# teste.net
KiCad netlist of a schematic drawn in EAGLE
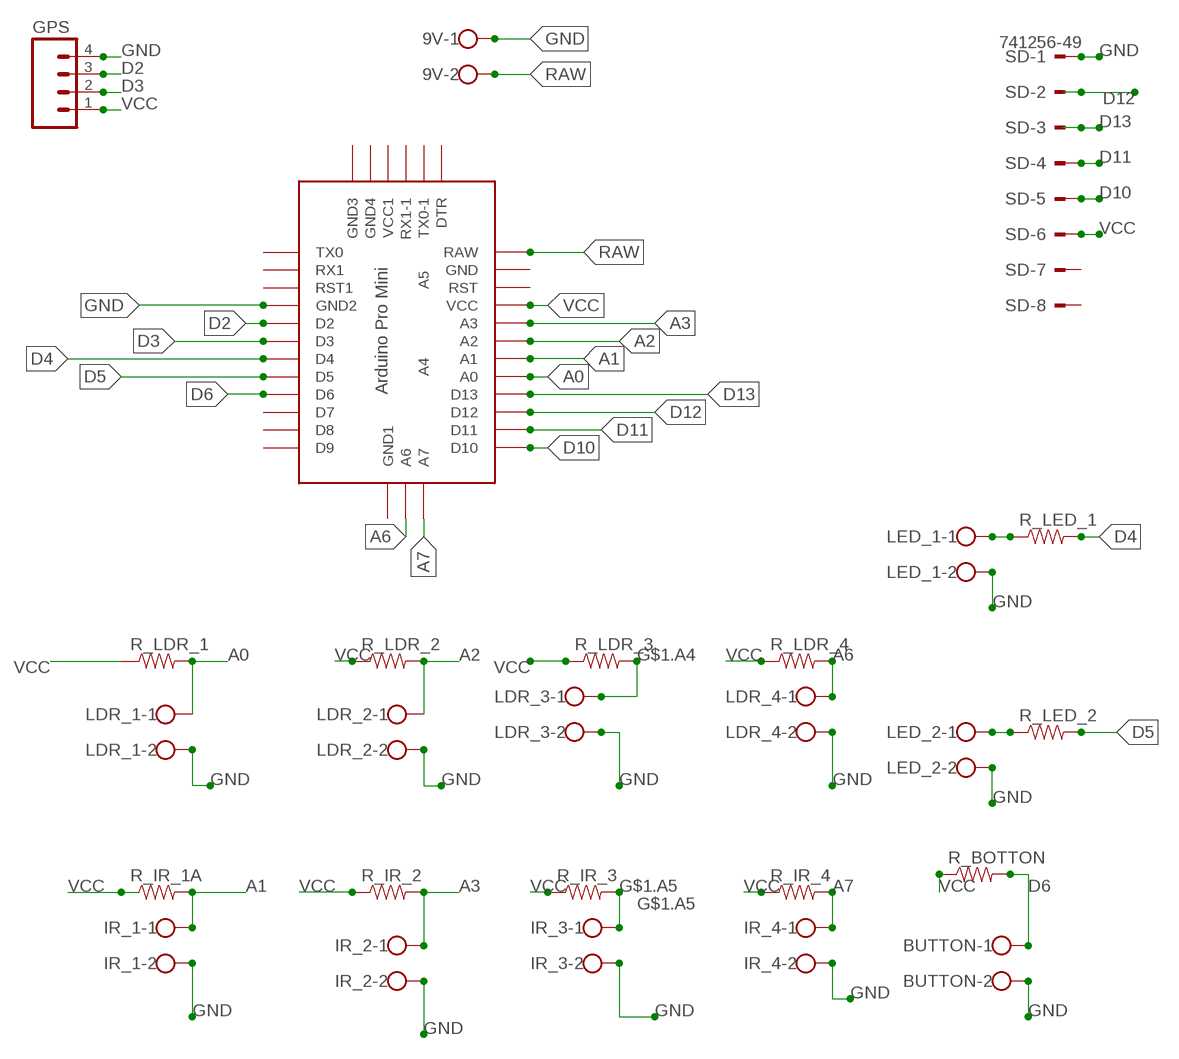
[diagram p0: schematic, sheet 1]

(export (version "E")
  (design (tool "Eeschema 10.0.6"))
  (components
    (comp (ref "9V")
      (value "W237-102")
      (footprint "eagle-import:W237-102")
      (fields (field (name "MPN") "237-102"))
      (libsource (lib "eagle-import") (part "W237-102"))
    )
    (comp (ref "BUTTON")
      (value "W237-102")
      (footprint "eagle-import:W237-102")
      (fields (field (name "MPN") "237-102"))
      (libsource (lib "eagle-import") (part "W237-102"))
    )
    (comp (ref "GPS")
      (value "M04LONGPADS")
      (footprint "eagle-import:1X04_LONGPADS")
      (libsource (lib "eagle-import") (part "M04LONGPADS"))
    )
    (comp (ref "IR_1")
      (value "W237-102")
      (footprint "eagle-import:W237-102")
      (fields (field (name "MPN") "237-102"))
      (libsource (lib "eagle-import") (part "W237-102"))
    )
    (comp (ref "IR_2")
      (value "W237-102")
      (footprint "eagle-import:W237-102")
      (fields (field (name "MPN") "237-102"))
      (libsource (lib "eagle-import") (part "W237-102"))
    )
    (comp (ref "IR_3")
      (value "W237-102")
      (footprint "eagle-import:W237-102")
      (fields (field (name "MPN") "237-102"))
      (libsource (lib "eagle-import") (part "W237-102"))
    )
    (comp (ref "IR_4")
      (value "W237-102")
      (footprint "eagle-import:W237-102")
      (fields (field (name "MPN") "237-102"))
      (libsource (lib "eagle-import") (part "W237-102"))
    )
    (comp (ref "LDR_1")
      (value "W237-102")
      (footprint "eagle-import:W237-102")
      (fields (field (name "MPN") "237-102"))
      (libsource (lib "eagle-import") (part "W237-102"))
    )
    (comp (ref "LDR_2")
      (value "W237-102")
      (footprint "eagle-import:W237-102")
      (fields (field (name "MPN") "237-102"))
      (libsource (lib "eagle-import") (part "W237-102"))
    )
    (comp (ref "LDR_3")
      (value "W237-102")
      (footprint "eagle-import:W237-102")
      (fields (field (name "MPN") "237-102"))
      (libsource (lib "eagle-import") (part "W237-102"))
    )
    (comp (ref "LDR_4")
      (value "W237-102")
      (footprint "eagle-import:W237-102")
      (fields (field (name "MPN") "237-102"))
      (libsource (lib "eagle-import") (part "W237-102"))
    )
    (comp (ref "LED_1")
      (value "W237-102")
      (footprint "eagle-import:W237-102")
      (fields (field (name "MPN") "237-102"))
      (libsource (lib "eagle-import") (part "W237-102"))
    )
    (comp (ref "LED_2")
      (value "W237-102")
      (footprint "eagle-import:W237-102")
      (fields (field (name "MPN") "237-102"))
      (libsource (lib "eagle-import") (part "W237-102"))
    )
    (comp (ref "R_BOTTON")
      (value "RESISTORAXIAL-0.3")
      (footprint "eagle-import:AXIAL-0.3")
      (libsource (lib "eagle-import") (part "RESISTORAXIAL-0.3"))
    )
    (comp (ref "R_IR_1A")
      (value "RESISTORAXIAL-0.3")
      (footprint "eagle-import:AXIAL-0.3")
      (libsource (lib "eagle-import") (part "RESISTORAXIAL-0.3"))
    )
    (comp (ref "R_IR_2")
      (value "RESISTORAXIAL-0.3")
      (footprint "eagle-import:AXIAL-0.3")
      (libsource (lib "eagle-import") (part "RESISTORAXIAL-0.3"))
    )
    (comp (ref "R_IR_3")
      (value "RESISTORAXIAL-0.3")
      (footprint "eagle-import:AXIAL-0.3")
      (libsource (lib "eagle-import") (part "RESISTORAXIAL-0.3"))
    )
    (comp (ref "R_IR_4")
      (value "RESISTORAXIAL-0.3")
      (footprint "eagle-import:AXIAL-0.3")
      (libsource (lib "eagle-import") (part "RESISTORAXIAL-0.3"))
    )
    (comp (ref "R_LDR_1")
      (value "RESISTORAXIAL-0.3")
      (footprint "eagle-import:AXIAL-0.3")
      (libsource (lib "eagle-import") (part "RESISTORAXIAL-0.3"))
    )
    (comp (ref "R_LDR_2")
      (value "RESISTORAXIAL-0.3")
      (footprint "eagle-import:AXIAL-0.3")
      (libsource (lib "eagle-import") (part "RESISTORAXIAL-0.3"))
    )
    (comp (ref "R_LDR_3")
      (value "RESISTORAXIAL-0.3")
      (footprint "eagle-import:AXIAL-0.3")
      (libsource (lib "eagle-import") (part "RESISTORAXIAL-0.3"))
    )
    (comp (ref "R_LDR_4")
      (value "RESISTORAXIAL-0.3")
      (footprint "eagle-import:AXIAL-0.3")
      (libsource (lib "eagle-import") (part "RESISTORAXIAL-0.3"))
    )
    (comp (ref "R_LED_1")
      (value "RESISTORAXIAL-0.3")
      (footprint "eagle-import:AXIAL-0.3")
      (libsource (lib "eagle-import") (part "RESISTORAXIAL-0.3"))
    )
    (comp (ref "R_LED_2")
      (value "RESISTORAXIAL-0.3")
      (footprint "eagle-import:AXIAL-0.3")
      (libsource (lib "eagle-import") (part "RESISTORAXIAL-0.3"))
    )
    (comp (ref "SD")
      (value "741256-49")
      (footprint "eagle-import:741256-49")
      (libsource (lib "eagle-import") (part "741256-49"))
    )
    (comp (ref "U$2")
      (value "ABK-PRO-MINI")
      (footprint "eagle-import:ABK-PRO-MINI")
      (libsource (lib "eagle-import") (part "ABK-PRO-MINI"))
    )
  )
  (nets
    (net (code "1") (name "/G$1.A4") (class "Default")
      (node (ref "LDR_3") (pin "1") (pinfunction "KL_1") (pintype "passive"))
      (node (ref "R_LDR_3") (pin "P$2") (pinfunction "2_P$2") (pintype "passive"))
    )
    (net (code "2") (name "/G$1.A5") (class "Default")
      (node (ref "IR_3") (pin "1") (pinfunction "KL_1") (pintype "passive"))
      (node (ref "R_IR_3") (pin "P$2") (pinfunction "2_P$2") (pintype "passive"))
    )
    (net (code "3") (name "A0") (class "Default")
      (node (ref "LDR_1") (pin "1") (pinfunction "KL_1") (pintype "passive"))
      (node (ref "R_LDR_1") (pin "P$2") (pinfunction "2_P$2") (pintype "passive"))
      (node (ref "U$2") (pin "A0") (pinfunction "A0_A0") (pintype "bidirectional"))
    )
    (net (code "4") (name "A1") (class "Default")
      (node (ref "IR_1") (pin "1") (pinfunction "KL_1") (pintype "passive"))
      (node (ref "R_IR_1A") (pin "P$2") (pinfunction "2_P$2") (pintype "passive"))
      (node (ref "U$2") (pin "A1") (pinfunction "A1_A1") (pintype "bidirectional"))
    )
    (net (code "5") (name "A2") (class "Default")
      (node (ref "LDR_2") (pin "1") (pinfunction "KL_1") (pintype "passive"))
      (node (ref "R_LDR_2") (pin "P$2") (pinfunction "2_P$2") (pintype "passive"))
      (node (ref "U$2") (pin "A2") (pinfunction "A2_A2") (pintype "bidirectional"))
    )
    (net (code "6") (name "A3") (class "Default")
      (node (ref "IR_2") (pin "1") (pinfunction "KL_1") (pintype "passive"))
      (node (ref "R_IR_2") (pin "P$2") (pinfunction "2_P$2") (pintype "passive"))
      (node (ref "U$2") (pin "A3") (pinfunction "A3_A3") (pintype "bidirectional"))
    )
    (net (code "7") (name "A6") (class "Default")
      (node (ref "LDR_4") (pin "1") (pinfunction "KL_1") (pintype "passive"))
      (node (ref "R_LDR_4") (pin "P$2") (pinfunction "2_P$2") (pintype "passive"))
      (node (ref "U$2") (pin "A6") (pinfunction "A6_A6") (pintype "bidirectional"))
    )
    (net (code "8") (name "A7") (class "Default")
      (node (ref "IR_4") (pin "1") (pinfunction "KL_1") (pintype "passive"))
      (node (ref "R_IR_4") (pin "P$2") (pinfunction "2_P$2") (pintype "passive"))
      (node (ref "U$2") (pin "A7") (pinfunction "A7_A7") (pintype "bidirectional"))
    )
    (net (code "9") (name "D2") (class "Default")
      (node (ref "GPS") (pin "3") (pinfunction "3_3") (pintype "passive"))
      (node (ref "U$2") (pin "D2") (pinfunction "D2_D2") (pintype "bidirectional"))
    )
    (net (code "10") (name "D3") (class "Default")
      (node (ref "GPS") (pin "2") (pinfunction "2_2") (pintype "passive"))
      (node (ref "U$2") (pin "D3") (pinfunction "D3_D3") (pintype "bidirectional"))
    )
    (net (code "11") (name "D4") (class "Default")
      (node (ref "R_LED_1") (pin "P$2") (pinfunction "2_P$2") (pintype "passive"))
      (node (ref "U$2") (pin "D4") (pinfunction "D4_D4") (pintype "bidirectional"))
    )
    (net (code "12") (name "D5") (class "Default")
      (node (ref "R_LED_2") (pin "P$2") (pinfunction "2_P$2") (pintype "passive"))
      (node (ref "U$2") (pin "D5") (pinfunction "D5_D5") (pintype "bidirectional"))
    )
    (net (code "13") (name "D6") (class "Default")
      (node (ref "BUTTON") (pin "1") (pinfunction "KL_1") (pintype "passive"))
      (node (ref "R_BOTTON") (pin "P$2") (pinfunction "2_P$2") (pintype "passive"))
      (node (ref "U$2") (pin "D6") (pinfunction "D6_D6") (pintype "bidirectional"))
    )
    (net (code "14") (name "D10") (class "Default")
      (node (ref "SD") (pin "5") (pinfunction "KL_5") (pintype "passive"))
      (node (ref "U$2") (pin "D10") (pinfunction "D10_D10") (pintype "bidirectional"))
    )
    (net (code "15") (name "D11") (class "Default")
      (node (ref "SD") (pin "4") (pinfunction "KL_4") (pintype "passive"))
      (node (ref "U$2") (pin "D11") (pinfunction "D11_D11") (pintype "bidirectional"))
    )
    (net (code "16") (name "D12") (class "Default")
      (node (ref "SD") (pin "2") (pinfunction "KL_2") (pintype "passive"))
      (node (ref "U$2") (pin "D12") (pinfunction "D12_D12") (pintype "bidirectional"))
    )
    (net (code "17") (name "D13") (class "Default")
      (node (ref "SD") (pin "3") (pinfunction "KL_3") (pintype "passive"))
      (node (ref "U$2") (pin "D13") (pinfunction "D13_D13") (pintype "bidirectional"))
    )
    (net (code "18") (name "GND") (class "Default")
      (node (ref "9V") (pin "1") (pinfunction "KL_1") (pintype "passive"))
      (node (ref "BUTTON") (pin "2") (pinfunction "KL_2") (pintype "passive"))
      (node (ref "GPS") (pin "4") (pinfunction "4_4") (pintype "passive"))
      (node (ref "IR_1") (pin "2") (pinfunction "KL_2") (pintype "passive"))
      (node (ref "IR_2") (pin "2") (pinfunction "KL_2") (pintype "passive"))
      (node (ref "IR_3") (pin "2") (pinfunction "KL_2") (pintype "passive"))
      (node (ref "IR_4") (pin "2") (pinfunction "KL_2") (pintype "passive"))
      (node (ref "LDR_1") (pin "2") (pinfunction "KL_2") (pintype "passive"))
      (node (ref "LDR_2") (pin "2") (pinfunction "KL_2") (pintype "passive"))
      (node (ref "LDR_3") (pin "2") (pinfunction "KL_2") (pintype "passive"))
      (node (ref "LDR_4") (pin "2") (pinfunction "KL_2") (pintype "passive"))
      (node (ref "LED_1") (pin "2") (pinfunction "KL_2") (pintype "passive"))
      (node (ref "LED_2") (pin "2") (pinfunction "KL_2") (pintype "passive"))
      (node (ref "SD") (pin "1") (pinfunction "KL_1") (pintype "passive"))
      (node (ref "U$2") (pin "GND1") (pinfunction "GND2_GND1") (pintype "bidirectional"))
    )
    (net (code "19") (name "Net-(LED_1A-KL)") (class "Default")
      (node (ref "LED_1") (pin "1") (pinfunction "KL_1") (pintype "passive"))
      (node (ref "R_LED_1") (pin "P$1") (pinfunction "1_P$1") (pintype "passive"))
    )
    (net (code "20") (name "Net-(LED_2A-KL)") (class "Default")
      (node (ref "LED_2") (pin "1") (pinfunction "KL_1") (pintype "passive"))
      (node (ref "R_LED_2") (pin "P$1") (pinfunction "1_P$1") (pintype "passive"))
    )
    (net (code "21") (name "RAW") (class "Default")
      (node (ref "9V") (pin "2") (pinfunction "KL_2") (pintype "passive"))
      (node (ref "U$2") (pin "RAW") (pinfunction "RAW_RAW") (pintype "bidirectional"))
    )
    (net (code "22") (name "VCC") (class "Default")
      (node (ref "GPS") (pin "1") (pinfunction "1_1") (pintype "passive"))
      (node (ref "R_BOTTON") (pin "P$1") (pinfunction "1_P$1") (pintype "passive"))
      (node (ref "R_IR_1A") (pin "P$1") (pinfunction "1_P$1") (pintype "passive"))
      (node (ref "R_IR_2") (pin "P$1") (pinfunction "1_P$1") (pintype "passive"))
      (node (ref "R_IR_3") (pin "P$1") (pinfunction "1_P$1") (pintype "passive"))
      (node (ref "R_IR_4") (pin "P$1") (pinfunction "1_P$1") (pintype "passive"))
      (node (ref "R_LDR_1") (pin "P$1") (pinfunction "1_P$1") (pintype "passive"))
      (node (ref "R_LDR_2") (pin "P$1") (pinfunction "1_P$1") (pintype "passive"))
      (node (ref "R_LDR_3") (pin "P$1") (pinfunction "1_P$1") (pintype "passive"))
      (node (ref "R_LDR_4") (pin "P$1") (pinfunction "1_P$1") (pintype "passive"))
      (node (ref "SD") (pin "6") (pinfunction "KL_6") (pintype "passive"))
      (node (ref "U$2") (pin "VCC") (pinfunction "VCC_VCC") (pintype "bidirectional"))
    )
    (net (code "23") (name "unconnected-(SDG-KL-Pad7)") (class "Default")
      (node (ref "SD") (pin "7") (pinfunction "KL_7") (pintype "passive"))
    )
    (net (code "24") (name "unconnected-(SDH-KL-Pad8)") (class "Default")
      (node (ref "SD") (pin "8") (pinfunction "KL_8") (pintype "passive"))
    )
    (net (code "25") (name "unconnected-(U$2-GND1-PadGND4)") (class "Default")
      (node (ref "U$2") (pin "GND4") (pinfunction "GND1_GND4") (pintype "bidirectional"))
    )
    (net (code "26") (name "unconnected-(U$2-GND3-PadGND2)") (class "Default")
      (node (ref "U$2") (pin "GND2") (pinfunction "GND3_GND2") (pintype "bidirectional"))
    )
    (net (code "27") (name "unconnected-(U$2-GND4-PadGND3)") (class "Default")
      (node (ref "U$2") (pin "GND3") (pinfunction "GND4_GND3") (pintype "bidirectional"))
    )
    (net (code "28") (name "unconnected-(U$2-PadA4)") (class "Default")
      (node (ref "U$2") (pin "A4") (pinfunction "A4_A4") (pintype "bidirectional"))
    )
    (net (code "29") (name "unconnected-(U$2-PadA5)") (class "Default")
      (node (ref "U$2") (pin "A5") (pinfunction "A5_A5") (pintype "bidirectional"))
    )
    (net (code "30") (name "unconnected-(U$2-PadD7)") (class "Default")
      (node (ref "U$2") (pin "D7") (pinfunction "D7_D7") (pintype "bidirectional"))
    )
    (net (code "31") (name "unconnected-(U$2-PadD8)") (class "Default")
      (node (ref "U$2") (pin "D8") (pinfunction "D8_D8") (pintype "bidirectional"))
    )
    (net (code "32") (name "unconnected-(U$2-PadD9)") (class "Default")
      (node (ref "U$2") (pin "D9") (pinfunction "D9_D9") (pintype "bidirectional"))
    )
    (net (code "33") (name "unconnected-(U$2-PadDTR)") (class "Default")
      (node (ref "U$2") (pin "DTR") (pinfunction "DTR_DTR") (pintype "bidirectional"))
    )
    (net (code "34") (name "unconnected-(U$2-PadGND)") (class "Default")
      (node (ref "U$2") (pin "GND") (pinfunction "GND_GND") (pintype "bidirectional"))
    )
    (net (code "35") (name "unconnected-(U$2-PadRST)") (class "Default")
      (node (ref "U$2") (pin "RST") (pinfunction "RST_RST") (pintype "bidirectional"))
    )
    (net (code "36") (name "unconnected-(U$2-PadRST1)") (class "Default")
      (node (ref "U$2") (pin "RST1") (pinfunction "RST1_RST1") (pintype "bidirectional"))
    )
    (net (code "37") (name "unconnected-(U$2-PadRX1)") (class "Default")
      (node (ref "U$2") (pin "RX1") (pinfunction "RX1_RX1") (pintype "bidirectional"))
    )
    (net (code "38") (name "unconnected-(U$2-PadRX1-1)") (class "Default")
      (node (ref "U$2") (pin "RX1-1") (pinfunction "RX1-1_RX1-1") (pintype "bidirectional"))
    )
    (net (code "39") (name "unconnected-(U$2-PadTX0)") (class "Default")
      (node (ref "U$2") (pin "TX0") (pinfunction "TX0_TX0") (pintype "bidirectional"))
    )
    (net (code "40") (name "unconnected-(U$2-PadTX0-1)") (class "Default")
      (node (ref "U$2") (pin "TX0-1") (pinfunction "TX0-1_TX0-1") (pintype "bidirectional"))
    )
    (net (code "41") (name "unconnected-(U$2-PadVCC1)") (class "Default")
      (node (ref "U$2") (pin "VCC1") (pinfunction "VCC1_VCC1") (pintype "bidirectional"))
    )
  )
)
